# rickroll.net
KiCad netlist of a schematic drawn in EAGLE
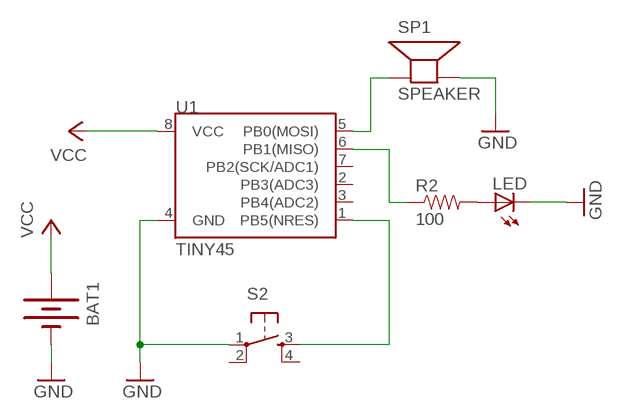
[diagram p0: schematic, sheet 1]

(export (version "E")
  (design (tool "Eeschema 10.0.6"))
  (components
    (comp (ref "BAT1")
      (value "BATTERY20PTH")
      (footprint "eagle-import:BATTCOM_20MM_PTH")
      (libsource (lib "eagle-import") (part "BATTERY20PTH"))
    )
    (comp (ref "LED")
      (value "LEDCHIPLED_0805")
      (footprint "eagle-import:CHIPLED_0805")
      (libsource (lib "eagle-import") (part "LEDCHIPLED_0805"))
    )
    (comp (ref "R2")
      (value "100")
      (footprint "eagle-import:0603-RES")
      (libsource (lib "eagle-import") (part "RESISTOR0603"))
    )
    (comp (ref "S2")
      (value "TAC_SWITCHPTH")
      (footprint "eagle-import:TACTILE-PTH")
      (libsource (lib "eagle-import") (part "TAC_SWITCHPTH"))
    )
    (comp (ref "SP1")
      (value "SPEAKER")
      (footprint "eagle-import:AL60P")
      (libsource (lib "eagle-import") (part "SPEAKER/AL60P"))
    )
    (comp (ref "U1")
      (value "TINY45")
      (footprint "eagle-import:DIP08")
      (libsource (lib "eagle-import") (part "ATTINY45TINY45-20-DIP"))
    )
  )
  (nets
    (net (code "1") (name "GND") (class "Default")
      (node (ref "BAT1") (pin "2") (pinfunction "-_2") (pintype "power_in"))
      (node (ref "LED") (pin "C") (pinfunction "C_C") (pintype "passive"))
      (node (ref "S2") (pin "1") (pinfunction "1_1") (pintype "passive"))
      (node (ref "SP1") (pin "2") (pinfunction "-_2") (pintype "passive"))
      (node (ref "U1") (pin "4") (pinfunction "GND_4") (pintype "bidirectional"))
    )
    (net (code "2") (name "Net-(LED-PadA)") (class "Default")
      (node (ref "LED") (pin "A") (pinfunction "A_A") (pintype "passive"))
      (node (ref "R2") (pin "2") (pinfunction "2_2") (pintype "passive"))
    )
    (net (code "3") (name "Net-(SP1-+)") (class "Default")
      (node (ref "SP1") (pin "1") (pinfunction "+_1") (pintype "passive"))
      (node (ref "U1") (pin "5") (pinfunction "PB0(MOSI)_5") (pintype "bidirectional"))
    )
    (net (code "4") (name "Net-(U1-PB1(MISO))") (class "Default")
      (node (ref "R2") (pin "1") (pinfunction "1_1") (pintype "passive"))
      (node (ref "U1") (pin "6") (pinfunction "PB1(MISO)_6") (pintype "bidirectional"))
    )
    (net (code "5") (name "Net-(U1-PB5(NRES))") (class "Default")
      (node (ref "S2") (pin "3") (pinfunction "3_3") (pintype "passive"))
      (node (ref "U1") (pin "1") (pinfunction "PB5(NRES)_1") (pintype "bidirectional"))
    )
    (net (code "6") (name "VCC") (class "Default")
      (node (ref "BAT1") (pin "1") (pinfunction "+_1") (pintype "power_in"))
      (node (ref "U1") (pin "8") (pinfunction "VCC_8") (pintype "bidirectional"))
    )
    (net (code "7") (name "unconnected-(S2-Pad2)") (class "Default")
      (node (ref "S2") (pin "2") (pinfunction "2_2") (pintype "passive"))
    )
    (net (code "8") (name "unconnected-(S2-Pad4)") (class "Default")
      (node (ref "S2") (pin "4") (pinfunction "4_4") (pintype "passive"))
    )
    (net (code "9") (name "unconnected-(U1-PB2(SCK{slash}ADC1)-Pad7)") (class "Default")
      (node (ref "U1") (pin "7") (pinfunction "PB2(SCK/ADC1)_7") (pintype "bidirectional"))
    )
    (net (code "10") (name "unconnected-(U1-PB3(ADC3)-Pad2)") (class "Default")
      (node (ref "U1") (pin "2") (pinfunction "PB3(ADC3)_2") (pintype "bidirectional"))
    )
    (net (code "11") (name "unconnected-(U1-PB4(ADC2)-Pad3)") (class "Default")
      (node (ref "U1") (pin "3") (pinfunction "PB4(ADC2)_3") (pintype "bidirectional"))
    )
  )
)
